# IR_robottino_schematics.net
KiCad netlist of a schematic drawn in Altium Designer
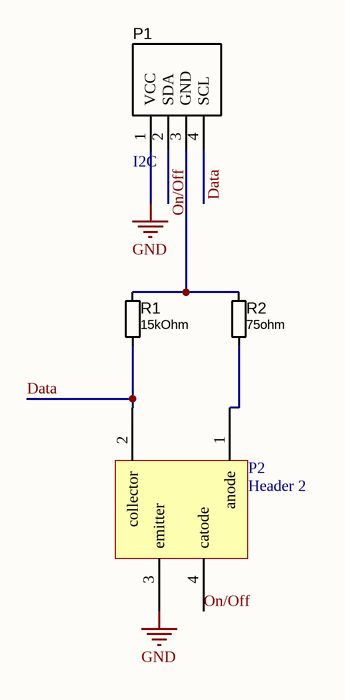
[diagram p0: IR_robottino_schematics.SchDoc]

(export (version "E")
  (design (tool "Eeschema 10.0.6"))
  (components
    (comp (ref "P1")
      (value "I2C")
      (footprint "TYCO/215079-4")
      (description "Micromatch I2C Connector")
      (libsource (lib "andylib") (part "Micromatch-I2C"))
    )
    (comp (ref "P2")
      (value "Header 2")
      (footprint "TCRT 5000")
      (description "Header, 2-Pin")
      (fields (field (name "PUBLISHER") "Altium Limited"))
      (libsource (lib "marcolib") (part "TCRT 5000"))
    )
    (comp (ref "R1")
      (value "15kOhm")
      (footprint "R/0805")
      (description "Resistor")
      (fields (field (name "PUBLISHER") "Altium Limited"))
      (libsource (lib "andylib") (part "R"))
    )
    (comp (ref "R2")
      (value "75ohm")
      (footprint "R/1206")
      (description "Resistor")
      (fields (field (name "PUBLISHER") "Altium Limited"))
      (libsource (lib "andylib") (part "R"))
    )
  )
  (nets
    (net (code "1") (name "/Data") (class "Default")
      (node (ref "P1") (pin "4") (pinfunction "SCL_4") (pintype "passive"))
      (node (ref "P2") (pin "2") (pinfunction "collector_2") (pintype "passive"))
      (node (ref "R1") (pin "1") (pinfunction "1_1") (pintype "passive"))
    )
    (net (code "2") (name "/On{slash}Off") (class "Default")
      (node (ref "P1") (pin "2") (pinfunction "SDA_2") (pintype "passive"))
      (node (ref "P2") (pin "4") (pinfunction "catode_4") (pintype "passive"))
    )
    (net (code "3") (name "GND") (class "Default")
      (node (ref "P1") (pin "1") (pinfunction "VCC_1") (pintype "passive"))
      (node (ref "P2") (pin "3") (pinfunction "emitter_3") (pintype "passive"))
    )
    (net (code "4") (name "Net-(P1-GND)") (class "Default")
      (node (ref "P1") (pin "3") (pinfunction "GND_3") (pintype "passive"))
      (node (ref "R1") (pin "2") (pinfunction "2_2") (pintype "passive"))
      (node (ref "R2") (pin "2") (pinfunction "2_2") (pintype "passive"))
    )
    (net (code "5") (name "Net-(P2-anode)") (class "Default")
      (node (ref "P2") (pin "1") (pinfunction "anode_1") (pintype "passive"))
      (node (ref "R2") (pin "1") (pinfunction "1_1") (pintype "passive"))
    )
  )
)
